# Vemos_Battry_Shield.net
KiCad netlist of a schematic drawn in Altium Designer
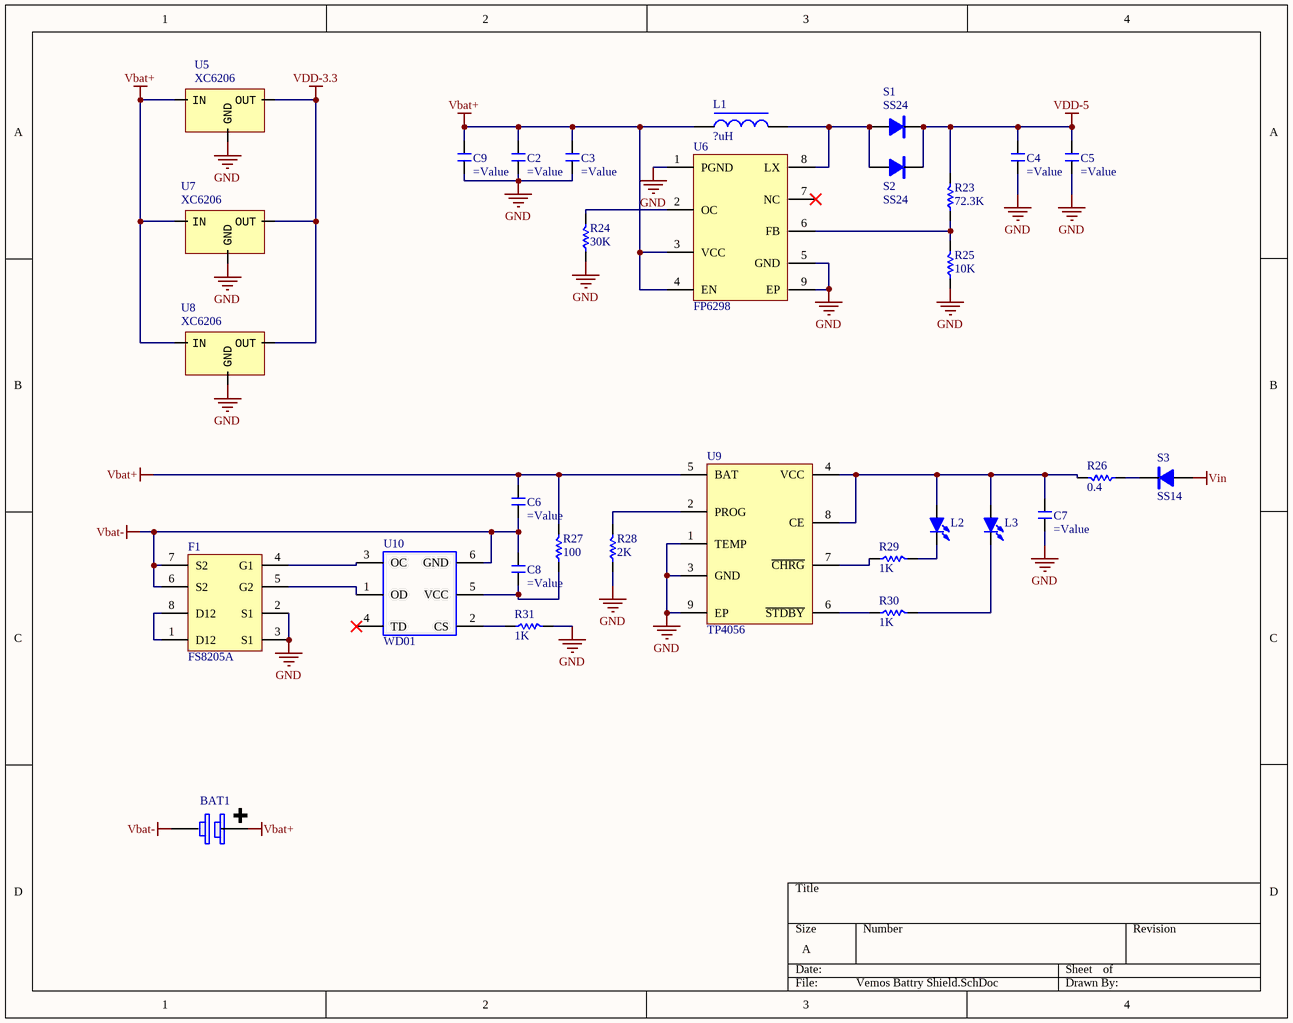
[diagram p0: Vemos Battry Shield.SchDoc]

(export (version "E")
  (design (tool "Eeschema 10.0.6"))
  (components
    (comp (ref "BAT1")
      (value "Battery 1850")
      (footprint "18650 SINGLE 2")
      (libsource (lib "Battery Holder") (part "Battery 1850"))
    )
    (comp (ref "C2")
      (value "~")
      (footprint "C 0603")
      (description "Non-polar patch capacitor")
      (fields (field (name "版权归属") "源创客"))
      (libsource (lib "Passive (Resistor-Capacitor-Inductor-Veristor-Ferrite)") (part "C"))
    )
    (comp (ref "C3")
      (value "~")
      (footprint "C 0603")
      (description "Non-polar patch capacitor")
      (fields (field (name "版权归属") "源创客"))
      (libsource (lib "Passive (Resistor-Capacitor-Inductor-Veristor-Ferrite)") (part "C"))
    )
    (comp (ref "C4")
      (value "~")
      (footprint "C 0603")
      (description "Non-polar patch capacitor")
      (fields (field (name "版权归属") "源创客"))
      (libsource (lib "Passive (Resistor-Capacitor-Inductor-Veristor-Ferrite)") (part "C"))
    )
    (comp (ref "C5")
      (value "~")
      (footprint "C 0603")
      (description "Non-polar patch capacitor")
      (fields (field (name "版权归属") "源创客"))
      (libsource (lib "Passive (Resistor-Capacitor-Inductor-Veristor-Ferrite)") (part "C"))
    )
    (comp (ref "C6")
      (value "~")
      (footprint "C 0603")
      (description "Non-polar patch capacitor")
      (fields (field (name "版权归属") "源创客"))
      (libsource (lib "Passive (Resistor-Capacitor-Inductor-Veristor-Ferrite)") (part "C"))
    )
    (comp (ref "C7")
      (value "~")
      (footprint "C 0603")
      (description "Non-polar patch capacitor")
      (fields (field (name "版权归属") "源创客"))
      (libsource (lib "Passive (Resistor-Capacitor-Inductor-Veristor-Ferrite)") (part "C"))
    )
    (comp (ref "C8")
      (value "~")
      (footprint "C 0603")
      (description "Non-polar patch capacitor")
      (fields (field (name "版权归属") "源创客"))
      (libsource (lib "Passive (Resistor-Capacitor-Inductor-Veristor-Ferrite)") (part "C"))
    )
    (comp (ref "C9")
      (value "~")
      (footprint "C 0603")
      (description "Non-polar patch capacitor")
      (fields (field (name "版权归属") "源创客"))
      (libsource (lib "Passive (Resistor-Capacitor-Inductor-Veristor-Ferrite)") (part "C"))
    )
    (comp (ref "F1")
      (value "FS8205A")
      (footprint "SSOP8_L")
      (description "Dual N-Channel Enhancement Mode Power MOSFET")
      (libsource (lib "Integrated Circuit") (part "FS8205A"))
    )
    (comp (ref "L1")
      (value "?uH")
      (footprint "WHC1040")
      (description "One-piece high current inductor")
      (libsource (lib "Passive (Resistor-Capacitor-Inductor-Veristor-Ferrite)") (part "L-WHC"))
    )
    (comp (ref "L2")
      (value "LED-SMD")
      (footprint "LED 0805G")
      (description "Patch LED")
      (fields (field (name "版权归属") "源创客"))
      (libsource (lib "LED") (part "LED-SMD"))
    )
    (comp (ref "L3")
      (value "LED-SMD")
      (footprint "LED 0805R")
      (description "Patch LED")
      (fields (field (name "版权归属") "源创客"))
      (libsource (lib "LED") (part "LED-SMD"))
    )
    (comp (ref "R23")
      (value "72.3K")
      (footprint "R 0603")
      (description "Chip resistor")
      (fields (field (name "版权归属") "源创客"))
      (libsource (lib "Passive (Resistor-Capacitor-Inductor-Veristor-Ferrite)") (part "R"))
    )
    (comp (ref "R24")
      (value "30K")
      (footprint "R 0603")
      (description "Chip resistor")
      (fields (field (name "版权归属") "源创客"))
      (libsource (lib "Passive (Resistor-Capacitor-Inductor-Veristor-Ferrite)") (part "R"))
    )
    (comp (ref "R25")
      (value "10K")
      (footprint "R 0603")
      (description "Chip resistor")
      (fields (field (name "版权归属") "源创客"))
      (libsource (lib "Passive (Resistor-Capacitor-Inductor-Veristor-Ferrite)") (part "R"))
    )
    (comp (ref "R26")
      (value "0.4")
      (footprint "R 0603")
      (description "Chip resistor")
      (fields (field (name "版权归属") "源创客"))
      (libsource (lib "Passive (Resistor-Capacitor-Inductor-Veristor-Ferrite)") (part "R"))
    )
    (comp (ref "R27")
      (value "100")
      (footprint "R 0603")
      (description "Chip resistor")
      (fields (field (name "版权归属") "源创客"))
      (libsource (lib "Passive (Resistor-Capacitor-Inductor-Veristor-Ferrite)") (part "R"))
    )
    (comp (ref "R28")
      (value "2K")
      (footprint "R 0603")
      (description "Chip resistor")
      (fields (field (name "版权归属") "源创客"))
      (libsource (lib "Passive (Resistor-Capacitor-Inductor-Veristor-Ferrite)") (part "R"))
    )
    (comp (ref "R29")
      (value "1K")
      (footprint "R 0603")
      (description "Chip resistor")
      (fields (field (name "版权归属") "源创客"))
      (libsource (lib "Passive (Resistor-Capacitor-Inductor-Veristor-Ferrite)") (part "R"))
    )
    (comp (ref "R30")
      (value "1K")
      (footprint "R 0603")
      (description "Chip resistor")
      (fields (field (name "版权归属") "源创客"))
      (libsource (lib "Passive (Resistor-Capacitor-Inductor-Veristor-Ferrite)") (part "R"))
    )
    (comp (ref "R31")
      (value "1K")
      (footprint "R 0603")
      (description "Chip resistor")
      (fields (field (name "版权归属") "源创客"))
      (libsource (lib "Passive (Resistor-Capacitor-Inductor-Veristor-Ferrite)") (part "R"))
    )
    (comp (ref "S1")
      (value "SS24")
      (footprint "SMA")
      (description "Schottky diodes")
      (fields (field (name "版权归属") "源创客"))
      (libsource (lib "Diode-Zener-Rectifier Bridge") (part "SS24"))
    )
    (comp (ref "S2")
      (value "SS24")
      (footprint "SMA")
      (description "Schottky diodes")
      (fields (field (name "版权归属") "源创客"))
      (libsource (lib "Diode-Zener-Rectifier Bridge") (part "SS24"))
    )
    (comp (ref "S3")
      (value "SS14")
      (footprint "SMA")
      (description "Schottky diodes")
      (fields (field (name "版权归属") "源创客"))
      (libsource (lib "Diode-Zener-Rectifier Bridge") (part "SS14"))
    )
    (comp (ref "U5")
      (value "XC6206")
      (footprint "SOT23-3N")
      (description "Power")
      (libsource (lib "Integrated Circuit") (part "XC6206"))
    )
    (comp (ref "U6")
      (value "FP6298")
      (footprint "SOP8_L-EP")
      (description "FP6298 Low-Noise 4.5A Step-Up Current Mode PWM")
      (libsource (lib "Integrated Circuit") (part "FP6298"))
    )
    (comp (ref "U7")
      (value "XC6206")
      (footprint "SOT23-3N")
      (description "Power")
      (libsource (lib "Integrated Circuit") (part "XC6206"))
    )
    (comp (ref "U8")
      (value "XC6206")
      (footprint "SOT23-3N")
      (description "Power")
      (libsource (lib "Integrated Circuit") (part "XC6206"))
    )
    (comp (ref "U9")
      (value "TP4056")
      (footprint "SOP8_M-EP")
      (description "Lithium battery charge management")
      (fields (field (name "版权归属") "源创客"))
      (libsource (lib "Integrated Circuit") (part "TP4056"))
    )
    (comp (ref "U10")
      (value "WD01")
      (footprint "SOT23-6M")
      (description "Lithium battery overcurrent protection IC")
      (fields (field (name "版权归属") "源创客"))
      (libsource (lib "Integrated Circuit") (part "WD01"))
    )
  )
  (nets
    (net (code "1") (name "GND") (class "Default")
      (node (ref "C2") (pin "1") (pinfunction "1_1") (pintype "passive"))
      (node (ref "C3") (pin "1") (pinfunction "1_1") (pintype "passive"))
      (node (ref "C4") (pin "1") (pinfunction "1_1") (pintype "passive"))
      (node (ref "C5") (pin "1") (pinfunction "1_1") (pintype "passive"))
      (node (ref "C7") (pin "1") (pinfunction "1_1") (pintype "passive"))
      (node (ref "C9") (pin "1") (pinfunction "1_1") (pintype "passive"))
      (node (ref "F1") (pin "2") (pinfunction "S1_2") (pintype "passive"))
      (node (ref "F1") (pin "3") (pinfunction "S1_3") (pintype "passive"))
      (node (ref "R24") (pin "1") (pinfunction "1_1") (pintype "passive"))
      (node (ref "R25") (pin "1") (pinfunction "1_1") (pintype "passive"))
      (node (ref "R28") (pin "1") (pinfunction "1_1") (pintype "passive"))
      (node (ref "R31") (pin "2") (pinfunction "2_2") (pintype "passive"))
      (node (ref "U5") (pin "1") (pinfunction "GND_1") (pintype "power_in"))
      (node (ref "U6") (pin "1") (pinfunction "PGND_1") (pintype "passive"))
      (node (ref "U6") (pin "5") (pinfunction "GND_5") (pintype "passive"))
      (node (ref "U6") (pin "9") (pinfunction "EP_9") (pintype "passive"))
      (node (ref "U7") (pin "1") (pinfunction "GND_1") (pintype "power_in"))
      (node (ref "U8") (pin "1") (pinfunction "GND_1") (pintype "power_in"))
      (node (ref "U9") (pin "1") (pinfunction "TEMP_1") (pintype "passive"))
      (node (ref "U9") (pin "3") (pinfunction "GND_3") (pintype "passive"))
      (node (ref "U9") (pin "9") (pinfunction "EP_9") (pintype "passive"))
    )
    (net (code "2") (name "Net-(F1-D12-Pad1)") (class "Default")
      (node (ref "F1") (pin "1") (pinfunction "D12_1") (pintype "passive"))
      (node (ref "F1") (pin "8") (pinfunction "D12_8") (pintype "passive"))
    )
    (net (code "3") (name "Net-(F1-G1)") (class "Default")
      (node (ref "F1") (pin "4") (pinfunction "G1_4") (pintype "passive"))
      (node (ref "U10") (pin "3") (pinfunction "OC_3") (pintype "passive"))
    )
    (net (code "4") (name "Net-(F1-G2)") (class "Default")
      (node (ref "F1") (pin "5") (pinfunction "G2_5") (pintype "passive"))
      (node (ref "U10") (pin "1") (pinfunction "OD_1") (pintype "passive"))
    )
    (net (code "5") (name "Net-(L2-A)") (class "Default")
      (node (ref "C7") (pin "2") (pinfunction "2_2") (pintype "passive"))
      (node (ref "L2") (pin "1") (pinfunction "A_1") (pintype "passive"))
      (node (ref "L3") (pin "1") (pinfunction "A_1") (pintype "passive"))
      (node (ref "R26") (pin "2") (pinfunction "2_2") (pintype "passive"))
      (node (ref "U9") (pin "4") (pinfunction "VCC_4") (pintype "passive"))
      (node (ref "U9") (pin "8") (pinfunction "CE_8") (pintype "passive"))
    )
    (net (code "6") (name "Net-(L2-K)") (class "Default")
      (node (ref "L2") (pin "2") (pinfunction "K_2") (pintype "passive"))
      (node (ref "R29") (pin "2") (pinfunction "2_2") (pintype "passive"))
    )
    (net (code "7") (name "Net-(L3-K)") (class "Default")
      (node (ref "L3") (pin "2") (pinfunction "K_2") (pintype "passive"))
      (node (ref "R30") (pin "2") (pinfunction "2_2") (pintype "passive"))
    )
    (net (code "8") (name "Net-(S1-A)") (class "Default")
      (node (ref "L1") (pin "2") (pinfunction "2_2") (pintype "passive"))
      (node (ref "S1") (pin "1") (pinfunction "A_1") (pintype "passive"))
      (node (ref "S2") (pin "1") (pinfunction "A_1") (pintype "passive"))
      (node (ref "U6") (pin "8") (pinfunction "LX_8") (pintype "passive"))
    )
    (net (code "9") (name "Net-(S3-K)") (class "Default")
      (node (ref "R26") (pin "1") (pinfunction "1_1") (pintype "passive"))
      (node (ref "S3") (pin "2") (pinfunction "K_2") (pintype "passive"))
    )
    (net (code "10") (name "Net-(U6-FB)") (class "Default")
      (node (ref "R23") (pin "1") (pinfunction "1_1") (pintype "passive"))
      (node (ref "R25") (pin "2") (pinfunction "2_2") (pintype "passive"))
      (node (ref "U6") (pin "6") (pinfunction "FB_6") (pintype "passive"))
    )
    (net (code "11") (name "Net-(U6-OC)") (class "Default")
      (node (ref "R24") (pin "2") (pinfunction "2_2") (pintype "passive"))
      (node (ref "U6") (pin "2") (pinfunction "OC_2") (pintype "passive"))
    )
    (net (code "12") (name "Net-(U9-PROG)") (class "Default")
      (node (ref "R28") (pin "2") (pinfunction "2_2") (pintype "passive"))
      (node (ref "U9") (pin "2") (pinfunction "PROG_2") (pintype "passive"))
    )
    (net (code "13") (name "Net-(U9-~{CHRG})") (class "Default")
      (node (ref "R29") (pin "1") (pinfunction "1_1") (pintype "passive"))
      (node (ref "U9") (pin "7") (pinfunction "~{CHRG}_7") (pintype "passive"))
    )
    (net (code "14") (name "Net-(U9-~{STDBY})") (class "Default")
      (node (ref "R30") (pin "1") (pinfunction "1_1") (pintype "passive"))
      (node (ref "U9") (pin "6") (pinfunction "~{STDBY}_6") (pintype "passive"))
    )
    (net (code "15") (name "Net-(U10-CS)") (class "Default")
      (node (ref "R31") (pin "1") (pinfunction "1_1") (pintype "passive"))
      (node (ref "U10") (pin "2") (pinfunction "CS_2") (pintype "passive"))
    )
    (net (code "16") (name "Net-(U10-VCC)") (class "Default")
      (node (ref "C8") (pin "1") (pinfunction "1_1") (pintype "passive"))
      (node (ref "R27") (pin "1") (pinfunction "1_1") (pintype "passive"))
      (node (ref "U10") (pin "5") (pinfunction "VCC_5") (pintype "passive"))
    )
    (net (code "17") (name "VDD-3.3") (class "Default")
      (node (ref "U5") (pin "2") (pinfunction "OUT_2") (pintype "power_in"))
      (node (ref "U7") (pin "2") (pinfunction "OUT_2") (pintype "power_in"))
      (node (ref "U8") (pin "2") (pinfunction "OUT_2") (pintype "power_in"))
    )
    (net (code "18") (name "VDD-5") (class "Default")
      (node (ref "C4") (pin "2") (pinfunction "2_2") (pintype "passive"))
      (node (ref "C5") (pin "2") (pinfunction "2_2") (pintype "passive"))
      (node (ref "R23") (pin "2") (pinfunction "2_2") (pintype "passive"))
      (node (ref "S1") (pin "2") (pinfunction "K_2") (pintype "passive"))
      (node (ref "S2") (pin "2") (pinfunction "K_2") (pintype "passive"))
    )
    (net (code "19") (name "Vbat+") (class "Default")
      (node (ref "BAT1") (pin "1") (pinfunction "+_1") (pintype "passive"))
      (node (ref "C2") (pin "2") (pinfunction "2_2") (pintype "passive"))
      (node (ref "C3") (pin "2") (pinfunction "2_2") (pintype "passive"))
      (node (ref "C6") (pin "2") (pinfunction "2_2") (pintype "passive"))
      (node (ref "C9") (pin "2") (pinfunction "2_2") (pintype "passive"))
      (node (ref "L1") (pin "1") (pinfunction "1_1") (pintype "passive"))
      (node (ref "R27") (pin "2") (pinfunction "2_2") (pintype "passive"))
      (node (ref "U5") (pin "3") (pinfunction "IN_3") (pintype "power_in"))
      (node (ref "U6") (pin "3") (pinfunction "VCC_3") (pintype "passive"))
      (node (ref "U6") (pin "4") (pinfunction "EN_4") (pintype "passive"))
      (node (ref "U7") (pin "3") (pinfunction "IN_3") (pintype "power_in"))
      (node (ref "U8") (pin "3") (pinfunction "IN_3") (pintype "power_in"))
      (node (ref "U9") (pin "5") (pinfunction "BAT_5") (pintype "passive"))
    )
    (net (code "20") (name "Vbat-") (class "Default")
      (node (ref "BAT1") (pin "2") (pinfunction "-_2") (pintype "passive"))
      (node (ref "C6") (pin "1") (pinfunction "1_1") (pintype "passive"))
      (node (ref "C8") (pin "2") (pinfunction "2_2") (pintype "passive"))
      (node (ref "F1") (pin "6") (pinfunction "S2_6") (pintype "passive"))
      (node (ref "F1") (pin "7") (pinfunction "S2_7") (pintype "passive"))
      (node (ref "U10") (pin "6") (pinfunction "GND_6") (pintype "passive"))
    )
    (net (code "21") (name "Vin") (class "Default")
      (node (ref "S3") (pin "1") (pinfunction "A_1") (pintype "passive"))
    )
    (net (code "22") (name "unconnected-(U6-NC-Pad7)") (class "Default")
      (node (ref "U6") (pin "7") (pinfunction "NC_7") (pintype "passive+no_connect"))
    )
    (net (code "23") (name "unconnected-(U10-TD-Pad4)") (class "Default")
      (node (ref "U10") (pin "4") (pinfunction "TD_4") (pintype "passive+no_connect"))
    )
  )
)
